# CPC1014_RELAY.net
KiCad netlist of a schematic drawn in Altium Designer
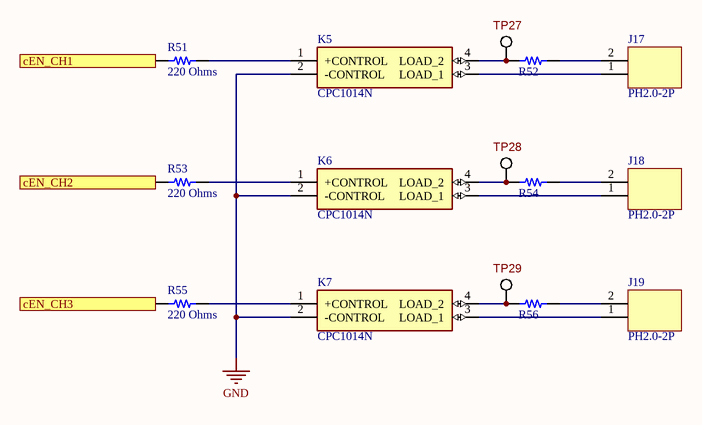
[diagram p0: CPC1014_RELAY.SchDoc]

(export (version "E")
  (design (tool "Eeschema 10.0.6"))
  (components
    (comp (ref "J17") (value "PH2.0-2P") (footprint "PH2.0-2P") (libsource (lib "PH") (part "PH2.0-2P")))
    (comp (ref "J18") (value "PH2.0-2P") (footprint "PH2.0-2P") (libsource (lib "PH") (part "PH2.0-2P")))
    (comp (ref "J19") (value "PH2.0-2P") (footprint "PH2.0-2P") (libsource (lib "PH") (part "PH2.0-2P")))
    (comp (ref "K5")
      (value "CPC1014N")
      (footprint "SamacSys:SOP254P610X218-4N")
      (description "Relay or Contactor")
      (fields (field (name "MOUSER PART NUMBER") "849-CPC1014N"))
      (libsource (lib "*") (part "CPC1014N"))
    )
    (comp (ref "K6")
      (value "CPC1014N")
      (footprint "SamacSys:SOP254P610X218-4N")
      (description "Relay or Contactor")
      (fields (field (name "MOUSER PART NUMBER") "849-CPC1014N"))
      (libsource (lib "*") (part "CPC1014N"))
    )
    (comp (ref "K7")
      (value "CPC1014N")
      (footprint "SamacSys:SOP254P610X218-4N")
      (description "Relay or Contactor")
      (fields (field (name "MOUSER PART NUMBER") "849-CPC1014N"))
      (libsource (lib "*") (part "CPC1014N"))
    )
    (comp (ref "R51")
      (value "220 Ohms")
      (footprint "RES 0805_2012")
      (description "RES SMD 220 OHM 1% 0.4W 0805")
      (fields (field (name "PART NUMBER") "ESR10EZPF2200") (field (name "MANUFACTURER") "Rohm Semiconductor"))
      (libsource (lib "Celestial Altium Library - altium_library") (part "Resistor"))
    )
    (comp (ref "R52")
      (value "~")
      (footprint "RES 0805_2012")
      (description "RES SMD 0 OHM JUMPER 1/8W 0805")
      (fields (field (name "PART NUMBER") "RC0805JR-070RP") (field (name "MANUFACTURER") "Yageo"))
      (libsource (lib "Celestial Altium Library - altium_library") (part "Resistor"))
    )
    (comp (ref "R53")
      (value "220 Ohms")
      (footprint "RES 0805_2012")
      (description "RES SMD 220 OHM 1% 0.4W 0805")
      (fields (field (name "PART NUMBER") "ESR10EZPF2200") (field (name "MANUFACTURER") "Rohm Semiconductor"))
      (libsource (lib "Celestial Altium Library - altium_library") (part "Resistor"))
    )
    (comp (ref "R54")
      (value "~")
      (footprint "RES 0805_2012")
      (description "RES SMD 0 OHM JUMPER 1/8W 0805")
      (fields (field (name "PART NUMBER") "RC0805JR-070RP") (field (name "MANUFACTURER") "Yageo"))
      (libsource (lib "Celestial Altium Library - altium_library") (part "Resistor"))
    )
    (comp (ref "R55")
      (value "220 Ohms")
      (footprint "RES 0805_2012")
      (description "RES SMD 220 OHM 1% 0.4W 0805")
      (fields (field (name "PART NUMBER") "ESR10EZPF2200") (field (name "MANUFACTURER") "Rohm Semiconductor"))
      (libsource (lib "Celestial Altium Library - altium_library") (part "Resistor"))
    )
    (comp (ref "R56")
      (value "~")
      (footprint "RES 0805_2012")
      (description "RES SMD 0 OHM JUMPER 1/8W 0805")
      (fields (field (name "PART NUMBER") "RC0805JR-070RP") (field (name "MANUFACTURER") "Yageo"))
      (libsource (lib "Celestial Altium Library - altium_library") (part "Resistor"))
    )
    (comp (ref "TP27")
      (value "PAD-1.1mm")
      (footprint "PAD-1.1mm")
      (description "1.1mm Pad for Plug-In or Receptacle")
      (fields (field (name "MANUFACTURER") "NONE"))
      (libsource (lib "misc") (part "PAD-1.1mm"))
    )
    (comp (ref "TP28")
      (value "PAD-1.1mm")
      (footprint "PAD-1.1mm")
      (description "1.1mm Pad for Plug-In or Receptacle")
      (fields (field (name "MANUFACTURER") "NONE"))
      (libsource (lib "misc") (part "PAD-1.1mm"))
    )
    (comp (ref "TP29")
      (value "PAD-1.1mm")
      (footprint "PAD-1.1mm")
      (description "1.1mm Pad for Plug-In or Receptacle")
      (fields (field (name "MANUFACTURER") "NONE"))
      (libsource (lib "misc") (part "PAD-1.1mm"))
    )
  )
  (nets
    (net (code "1") (name "/cEN_CH1") (class "Default")
      (node (ref "R51") (pin "2") (pinfunction "2_2") (pintype "passive"))
    )
    (net (code "2") (name "/cEN_CH2") (class "Default")
      (node (ref "R53") (pin "2") (pinfunction "2_2") (pintype "passive"))
    )
    (net (code "3") (name "/cEN_CH3") (class "Default")
      (node (ref "R55") (pin "2") (pinfunction "2_2") (pintype "passive"))
    )
    (net (code "4") (name "GND") (class "Default")
      (node (ref "K5") (pin "2") (pinfunction "-CONTROL_2") (pintype "power_in"))
      (node (ref "K6") (pin "2") (pinfunction "-CONTROL_2") (pintype "power_in"))
      (node (ref "K7") (pin "2") (pinfunction "-CONTROL_2") (pintype "power_in"))
    )
    (net (code "5") (name "Net-(J17-Pad2)") (class "Default")
      (node (ref "J17") (pin "2") (pinfunction "2_2") (pintype "passive"))
      (node (ref "R52") (pin "2") (pinfunction "2_2") (pintype "passive"))
    )
    (net (code "6") (name "Net-(J18-Pad2)") (class "Default")
      (node (ref "J18") (pin "2") (pinfunction "2_2") (pintype "passive"))
      (node (ref "R54") (pin "2") (pinfunction "2_2") (pintype "passive"))
    )
    (net (code "7") (name "Net-(J19-Pad2)") (class "Default")
      (node (ref "J19") (pin "2") (pinfunction "2_2") (pintype "passive"))
      (node (ref "R56") (pin "2") (pinfunction "2_2") (pintype "passive"))
    )
    (net (code "8") (name "Net-(K5-+CONTROL)") (class "Default")
      (node (ref "K5") (pin "1") (pinfunction "+CONTROL_1") (pintype "power_in"))
      (node (ref "R51") (pin "1") (pinfunction "1_1") (pintype "passive"))
    )
    (net (code "9") (name "Net-(K5-LOAD_1)") (class "Default")
      (node (ref "J17") (pin "1") (pinfunction "1_1") (pintype "passive"))
      (node (ref "K5") (pin "3") (pinfunction "LOAD_1_3") (pintype "bidirectional"))
    )
    (net (code "10") (name "Net-(K5-LOAD_2)") (class "Default")
      (node (ref "K5") (pin "4") (pinfunction "LOAD_2_4") (pintype "bidirectional"))
      (node (ref "R52") (pin "1") (pinfunction "1_1") (pintype "passive"))
      (node (ref "TP27") (pin "1") (pintype "passive"))
    )
    (net (code "11") (name "Net-(K6-+CONTROL)") (class "Default")
      (node (ref "K6") (pin "1") (pinfunction "+CONTROL_1") (pintype "power_in"))
      (node (ref "R53") (pin "1") (pinfunction "1_1") (pintype "passive"))
    )
    (net (code "12") (name "Net-(K6-LOAD_1)") (class "Default")
      (node (ref "J18") (pin "1") (pinfunction "1_1") (pintype "passive"))
      (node (ref "K6") (pin "3") (pinfunction "LOAD_1_3") (pintype "bidirectional"))
    )
    (net (code "13") (name "Net-(K6-LOAD_2)") (class "Default")
      (node (ref "K6") (pin "4") (pinfunction "LOAD_2_4") (pintype "bidirectional"))
      (node (ref "R54") (pin "1") (pinfunction "1_1") (pintype "passive"))
      (node (ref "TP28") (pin "1") (pintype "passive"))
    )
    (net (code "14") (name "Net-(K7-+CONTROL)") (class "Default")
      (node (ref "K7") (pin "1") (pinfunction "+CONTROL_1") (pintype "power_in"))
      (node (ref "R55") (pin "1") (pinfunction "1_1") (pintype "passive"))
    )
    (net (code "15") (name "Net-(K7-LOAD_1)") (class "Default")
      (node (ref "J19") (pin "1") (pinfunction "1_1") (pintype "passive"))
      (node (ref "K7") (pin "3") (pinfunction "LOAD_1_3") (pintype "bidirectional"))
    )
    (net (code "16") (name "Net-(K7-LOAD_2)") (class "Default")
      (node (ref "K7") (pin "4") (pinfunction "LOAD_2_4") (pintype "bidirectional"))
      (node (ref "R56") (pin "1") (pinfunction "1_1") (pintype "passive"))
      (node (ref "TP29") (pin "1") (pintype "passive"))
    )
  )
)
